# ACS723_Low_Current_Sensor.net
KiCad netlist of a schematic drawn in EAGLE
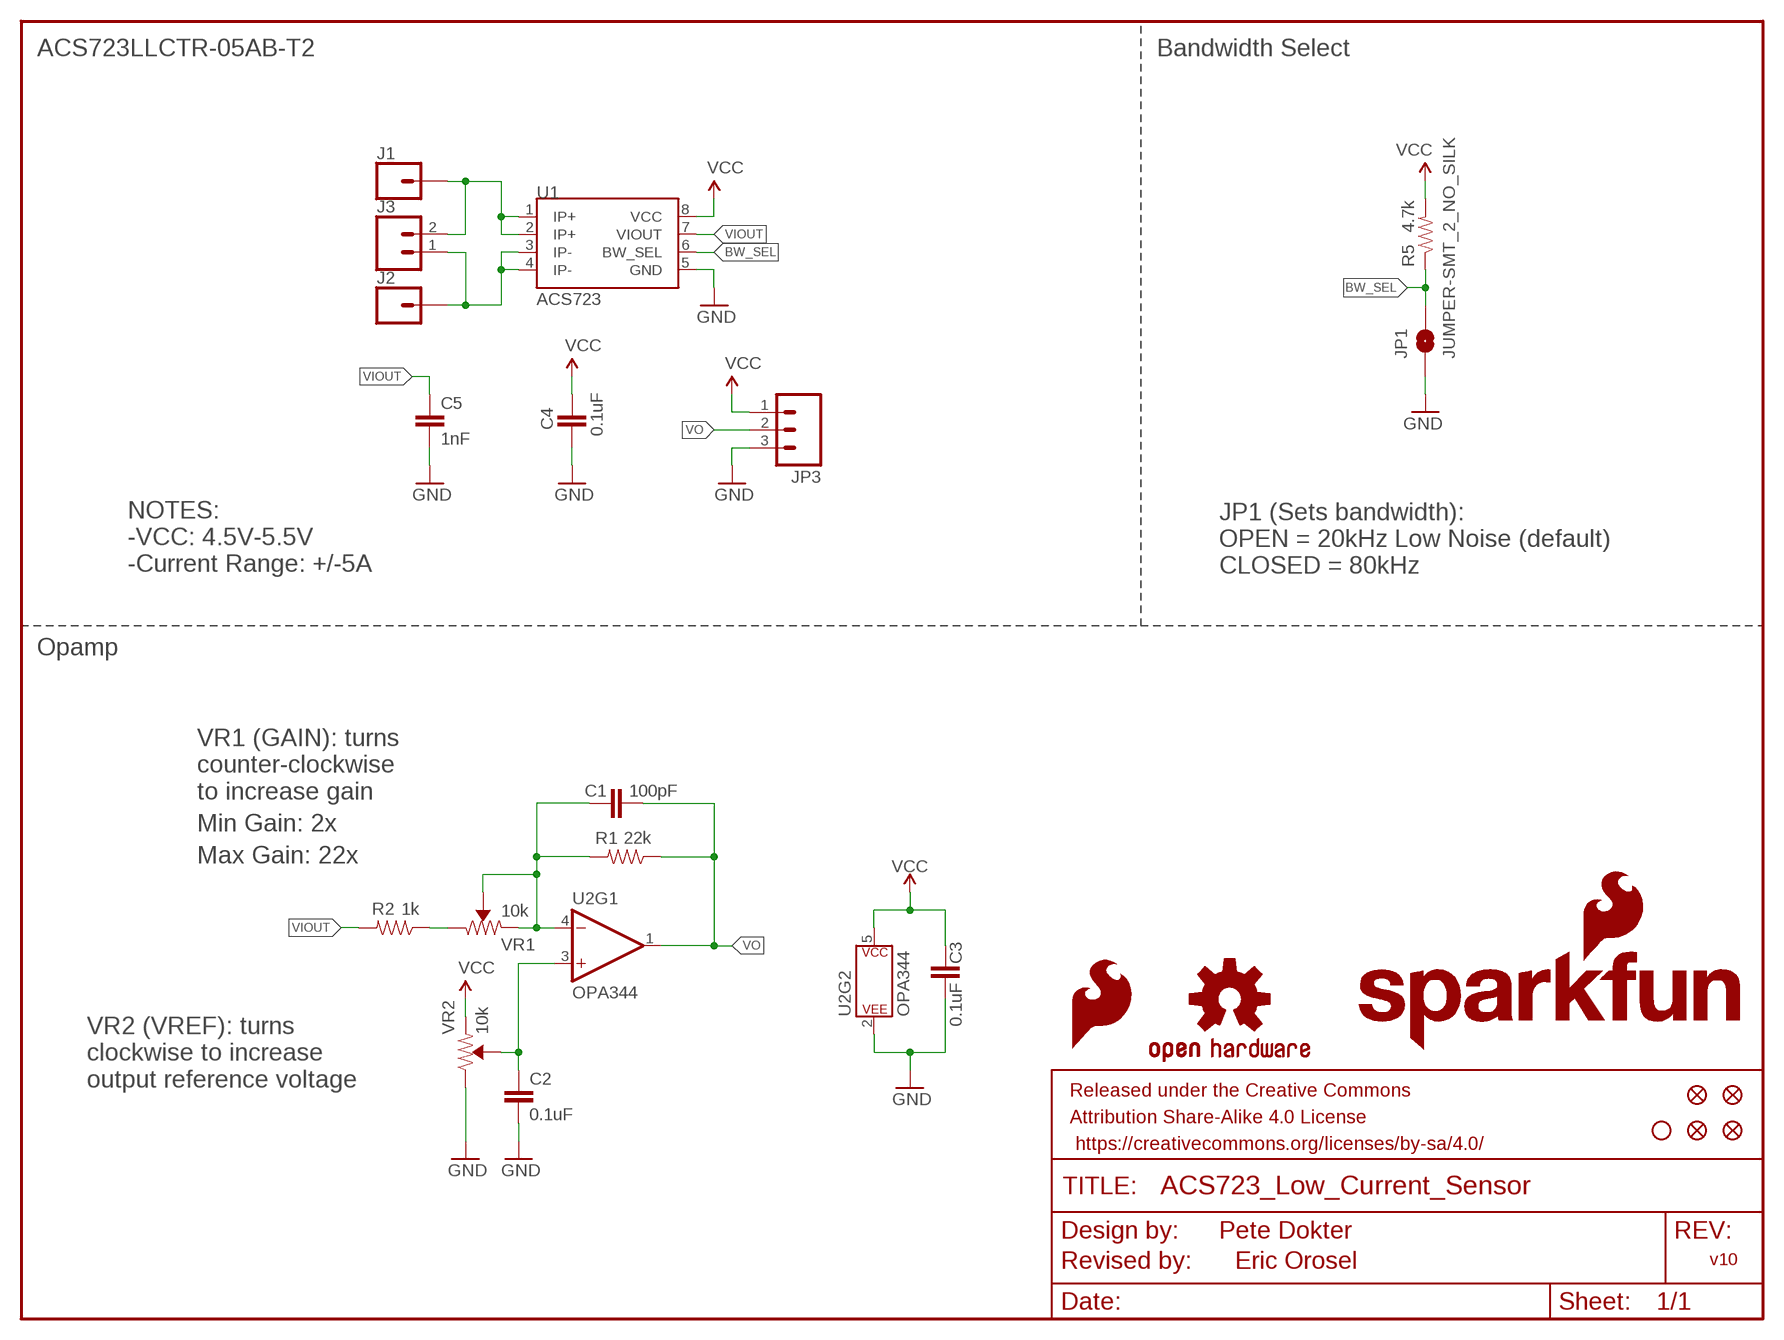
[diagram p0: schematic, sheet 1]

(export (version "E")
  (design (tool "Eeschema 10.0.6"))
  (components
    (comp (ref "C1")
      (value "100pF")
      (footprint "eagle-import:0603")
      (libsource (lib "eagle-import") (part "100PF-0603-50V-5%"))
    )
    (comp (ref "C2")
      (value "0.1uF")
      (footprint "eagle-import:0603")
      (libsource (lib "eagle-import") (part "0.1UF-0603-25V-(+80/-20%)"))
    )
    (comp (ref "C3")
      (value "0.1uF")
      (footprint "eagle-import:0603")
      (libsource (lib "eagle-import") (part "0.1UF-0603-25V-(+80/-20%)"))
    )
    (comp (ref "C4")
      (value "0.1uF")
      (footprint "eagle-import:0603")
      (libsource (lib "eagle-import") (part "0.1UF-0603-25V-(+80/-20%)"))
    )
    (comp (ref "C5")
      (value "1nF")
      (footprint "eagle-import:0603")
      (libsource (lib "eagle-import") (part "1.0NF/1000PF-0603-50V-10%"))
    )
    (comp (ref "FD1")
      (value "FIDUCIAL1X2")
      (footprint "eagle-import:FIDUCIAL-1X2")
      (libsource (lib "eagle-import") (part "FIDUCIAL1X2"))
    )
    (comp (ref "FD2")
      (value "FIDUCIAL1X2")
      (footprint "eagle-import:FIDUCIAL-1X2")
      (libsource (lib "eagle-import") (part "FIDUCIAL1X2"))
    )
    (comp (ref "FD3")
      (value "FIDUCIAL1X2")
      (footprint "eagle-import:FIDUCIAL-1X2")
      (libsource (lib "eagle-import") (part "FIDUCIAL1X2"))
    )
    (comp (ref "FD4")
      (value "FIDUCIAL1X2")
      (footprint "eagle-import:FIDUCIAL-1X2")
      (libsource (lib "eagle-import") (part "FIDUCIAL1X2"))
    )
    (comp (ref "FRAME1")
      (value "FRAME-LETTER")
      (footprint "eagle-import:CREATIVE_COMMONS")
      (libsource (lib "eagle-import") (part "FRAME-LETTER"))
    )
    (comp (ref "H1")
      (value "STAND-OFFTIGHT")
      (footprint "eagle-import:STAND-OFF-TIGHT")
      (libsource (lib "eagle-import") (part "STAND-OFFTIGHT"))
    )
    (comp (ref "J1")
      (value "CONN_01SMTSO-256-ET-0.165DIA")
      (footprint "eagle-import:SMTSO-256-ET-0.165DIA")
      (libsource (lib "eagle-import") (part "CONN_01SMTSO-256-ET-0.165DIA"))
    )
    (comp (ref "J2")
      (value "CONN_01SMTSO-256-ET-0.165DIA")
      (footprint "eagle-import:SMTSO-256-ET-0.165DIA")
      (libsource (lib "eagle-import") (part "CONN_01SMTSO-256-ET-0.165DIA"))
    )
    (comp (ref "J3")
      (value "CONN_021X02_NO_SILK")
      (footprint "eagle-import:1X02_NO_SILK")
      (libsource (lib "eagle-import") (part "CONN_021X02_NO_SILK"))
    )
    (comp (ref "JP1")
      (value "JUMPER-SMT_2_NO_SILK")
      (footprint "eagle-import:SMT-JUMPER_2_NO_SILK")
      (libsource (lib "eagle-import") (part "JUMPER-SMT_2_NO_SILK"))
    )
    (comp (ref "JP3")
      (value "M03PTH")
      (footprint "eagle-import:1X03")
      (libsource (lib "eagle-import") (part "M03PTH"))
    )
    (comp (ref "LOGO1")
      (value "SFE_LOGO_NAME_FLAME.1_INCH")
      (footprint "eagle-import:SFE_LOGO_NAME_FLAME_.1")
      (libsource (lib "eagle-import") (part "SFE_LOGO_NAME_FLAME.1_INCH"))
    )
    (comp (ref "LOGO2")
      (value "OSHW-LOGOS")
      (footprint "eagle-import:OSHW-LOGO-S")
      (libsource (lib "eagle-import") (part "OSHW-LOGOS"))
    )
    (comp (ref "LOGO3")
      (value "SFE_LOGO_FLAME.1_INCH")
      (footprint "eagle-import:SFE_LOGO_FLAME_.1")
      (libsource (lib "eagle-import") (part "SFE_LOGO_FLAME.1_INCH"))
    )
    (comp (ref "R1")
      (value "22k")
      (footprint "eagle-import:0603")
      (libsource (lib "eagle-import") (part "22KOHM-0603-1/10W-1%"))
    )
    (comp (ref "R2")
      (value "1k")
      (footprint "eagle-import:0603")
      (libsource (lib "eagle-import") (part "1KOHM-0603-1/10W-1%"))
    )
    (comp (ref "R5")
      (value "4.7k")
      (footprint "eagle-import:0603")
      (libsource (lib "eagle-import") (part "4.7KOHM-0603-1/10W-1%"))
    )
    (comp (ref "U1")
      (value "ACS723")
      (footprint "eagle-import:SO08")
      (fields (field (name "PART_#") "ACS723ACS723LLCTR-05AB-T2"))
      (libsource (lib "eagle-import") (part "ACS723"))
    )
    (comp (ref "U2")
      (value "OPA344")
      (footprint "eagle-import:SOT23-5")
      (libsource (lib "eagle-import") (part "OPA344"))
    )
    (comp (ref "VR1")
      (value "10k")
      (footprint "eagle-import:TRIMPOT-SMD-TC33X")
      (libsource (lib "eagle-import") (part "TRIMPOT-SMD-3MM-OPEN-1/10W-25%"))
    )
    (comp (ref "VR2")
      (value "10k")
      (footprint "eagle-import:TRIMPOT-SMD-TC33X")
      (libsource (lib "eagle-import") (part "TRIMPOT-SMD-3MM-OPEN-1/10W-25%"))
    )
  )
  (nets
    (net (code "1") (name "BW_SEL") (class "Default")
      (node (ref "JP1") (pin "2") (pinfunction "2_2") (pintype "passive"))
      (node (ref "R5") (pin "1") (pinfunction "1_1") (pintype "passive"))
      (node (ref "U1") (pin "6") (pinfunction "BW_SEL_6") (pintype "bidirectional"))
    )
    (net (code "2") (name "GND") (class "Default")
      (node (ref "C2") (pin "2") (pinfunction "2_2") (pintype "passive"))
      (node (ref "C3") (pin "2") (pinfunction "2_2") (pintype "passive"))
      (node (ref "C4") (pin "1") (pinfunction "1_1") (pintype "passive"))
      (node (ref "C5") (pin "2") (pinfunction "2_2") (pintype "passive"))
      (node (ref "JP1") (pin "1") (pinfunction "1_1") (pintype "passive"))
      (node (ref "JP3") (pin "3") (pinfunction "3_3") (pintype "passive"))
      (node (ref "U1") (pin "5") (pinfunction "GND_5") (pintype "bidirectional"))
      (node (ref "U2") (pin "2") (pinfunction "P$V-_2") (pintype "bidirectional"))
      (node (ref "VR2") (pin "1") (pinfunction "CW_1") (pintype "passive"))
    )
    (net (code "3") (name "Net-(J1-1)") (class "Default")
      (node (ref "J1") (pin "P$1") (pinfunction "1_P$1") (pintype "passive"))
      (node (ref "J3") (pin "2") (pinfunction "2_2") (pintype "passive"))
      (node (ref "U1") (pin "1") (pinfunction "IP+_1") (pintype "input"))
      (node (ref "U1") (pin "2") (pinfunction "IP+_2") (pintype "input"))
    )
    (net (code "4") (name "Net-(J2-1)") (class "Default")
      (node (ref "J2") (pin "P$1") (pinfunction "1_P$1") (pintype "passive"))
      (node (ref "J3") (pin "1") (pinfunction "1_1") (pintype "passive"))
      (node (ref "U1") (pin "3") (pinfunction "IP-_3") (pintype "bidirectional"))
      (node (ref "U1") (pin "4") (pinfunction "IP-_4") (pintype "bidirectional"))
    )
    (net (code "5") (name "Net-(U2A-+IN)") (class "Default")
      (node (ref "C2") (pin "1") (pinfunction "1_1") (pintype "passive"))
      (node (ref "U2") (pin "3") (pinfunction "+IN_3") (pintype "input"))
      (node (ref "VR2") (pin "2") (pinfunction "WIPER_2") (pintype "passive"))
    )
    (net (code "6") (name "Net-(U2A--IN)") (class "Default")
      (node (ref "C1") (pin "2") (pinfunction "2_2") (pintype "passive"))
      (node (ref "R1") (pin "2") (pinfunction "2_2") (pintype "passive"))
      (node (ref "U2") (pin "4") (pinfunction "-IN_4") (pintype "input"))
      (node (ref "VR1") (pin "2") (pinfunction "WIPER_2") (pintype "passive"))
      (node (ref "VR1") (pin "3") (pinfunction "CCW_3") (pintype "passive"))
    )
    (net (code "7") (name "Net-(VR1-CW)") (class "Default")
      (node (ref "R2") (pin "1") (pinfunction "1_1") (pintype "passive"))
      (node (ref "VR1") (pin "1") (pinfunction "CW_1") (pintype "passive"))
    )
    (net (code "8") (name "VCC") (class "Default")
      (node (ref "C3") (pin "1") (pinfunction "1_1") (pintype "passive"))
      (node (ref "C4") (pin "2") (pinfunction "2_2") (pintype "passive"))
      (node (ref "JP3") (pin "1") (pinfunction "1_1") (pintype "passive"))
      (node (ref "R5") (pin "2") (pinfunction "2_2") (pintype "passive"))
      (node (ref "U1") (pin "8") (pinfunction "VCC_8") (pintype "bidirectional"))
      (node (ref "U2") (pin "5") (pinfunction "P$V+_5") (pintype "bidirectional"))
      (node (ref "VR2") (pin "3") (pinfunction "CCW_3") (pintype "passive"))
    )
    (net (code "9") (name "VIOUT") (class "Default")
      (node (ref "C5") (pin "1") (pinfunction "1_1") (pintype "passive"))
      (node (ref "R2") (pin "2") (pinfunction "2_2") (pintype "passive"))
      (node (ref "U1") (pin "7") (pinfunction "VIOUT_7") (pintype "bidirectional"))
    )
    (net (code "10") (name "VO") (class "Default")
      (node (ref "C1") (pin "1") (pinfunction "1_1") (pintype "passive"))
      (node (ref "JP3") (pin "2") (pinfunction "2_2") (pintype "passive"))
      (node (ref "R1") (pin "1") (pinfunction "1_1") (pintype "passive"))
      (node (ref "U2") (pin "1") (pinfunction "OUT_1") (pintype "output"))
    )
  )
)
